# UC3843_SWITCHING_POWER_SUPPLY_V1.net
KiCad netlist of a schematic drawn in Altium Designer
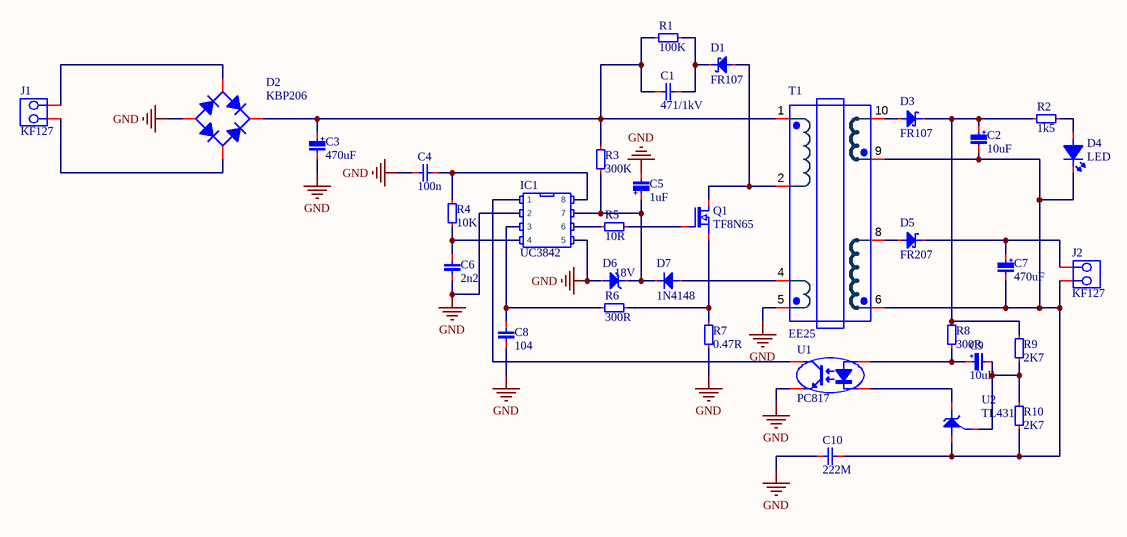
[diagram p0: UC3843_SWITCHING_POWER_SUPPLY_V1.SchDoc]

(export (version "E")
  (design (tool "Eeschema 10.0.6"))
  (components
    (comp (ref "C1")
      (value "471/1kV")
      (footprint "CAP_Ceramic_5MM")
      (libsource (lib "MyAltiumLibrary") (part "Capacitors(Disc)"))
    )
    (comp (ref "C2")
      (value "10uF")
      (footprint "CAP_RAD_D05x11")
      (libsource (lib "MyAltiumLibrary") (part "Capacitor(Radian)"))
    )
    (comp (ref "C3")
      (value "470uF")
      (footprint "CAP_RAD_D10x12.5")
      (libsource (lib "MyAltiumLibrary") (part "Capacitor(Radian)"))
    )
    (comp (ref "C4")
      (value "100n")
      (footprint "CAP_Ceramic_2.5MM")
      (libsource (lib "MyAltiumLibrary") (part "Capacitors(Disc)"))
    )
    (comp (ref "C5")
      (value "1uF")
      (footprint "CAP_RAD_D05x11")
      (libsource (lib "") (part "Capacitor(Radian)_1"))
    )
    (comp (ref "C6")
      (value "2n2")
      (footprint "CAP_Ceramic_2.5MM")
      (libsource (lib "") (part "Capacitors(Disc)_1"))
    )
    (comp (ref "C7")
      (value "470uF")
      (footprint "CAP_RAD_D10x12.5")
      (libsource (lib "MyAltiumLibrary") (part "Capacitor(Radian)"))
    )
    (comp (ref "C8")
      (value "104")
      (footprint "CAP_Ceramic_2.5MM")
      (libsource (lib "") (part "Capacitors(Disc)_1"))
    )
    (comp (ref "C9")
      (value "10uF")
      (footprint "CAP_RAD_D05x11")
      (libsource (lib "") (part "Capacitor(Radian)_2"))
    )
    (comp (ref "C10")
      (value "222M")
      (footprint "CAP_Ceramic_473M_9.65mm")
      (libsource (lib "") (part "Capacitors(Disc)_2"))
    )
    (comp (ref "D1")
      (value "FR107")
      (footprint "DO-204AL-BK")
      (description "1A 1000V")
      (libsource (lib "MyAltiumLibrary") (part "Diode-FR107"))
    )
    (comp (ref "D2")
      (value "KBP206")
      (footprint "DIODE-KBP206")
      (libsource (lib "MyAltiumLibrary") (part "Diode-KBP206"))
    )
    (comp (ref "D3")
      (value "FR107")
      (footprint "DO-204AL-BK")
      (description "1A 1000V")
      (libsource (lib "MyAltiumLibrary") (part "Diode-FR107"))
    )
    (comp (ref "D4") (value "LED") (footprint "LED_5MM") (libsource (lib "MyAltiumLibrary") (part "LED 5MM")))
    (comp (ref "D5")
      (value "FR207")
      (footprint "DO-204AC-BK")
      (libsource (lib "MyAltiumLibrary") (part "Diode-FR207"))
    )
    (comp (ref "D6")
      (value "18V")
      (footprint "DO-204AL-RD")
      (libsource (lib "MyAltiumLibrary") (part "Diode-Zener"))
    )
    (comp (ref "D7")
      (value "1N4148")
      (footprint "DO-204AH-RD")
      (description "The fast switching diode")
      (libsource (lib "MyAltiumLibrary") (part "Diode-1N4148"))
    )
    (comp (ref "IC1")
      (value "UC3842")
      (footprint "DIP-8")
      (description "Operating Frequency up to 500KHz")
      (libsource (lib "MyAltiumLibrary") (part "SMPS-UC3842"))
    )
    (comp (ref "J1")
      (value "KF127")
      (footprint "DG127-5.0-02P-14-00AH")
      (libsource (lib "MyAltiumLibrary") (part "DG127-5.0-02P-14-00AH"))
    )
    (comp (ref "J2")
      (value "KF127")
      (footprint "DG127-5.0-02P-14-00AH")
      (libsource (lib "") (part "DG127-5.0-02P-14-00AH_1"))
    )
    (comp (ref "Q1")
      (value "TF8N65")
      (footprint "TO-220F-HEAT-SINK")
      (description "VDS = 650V\r\n ID (at VGS=10V) 8A\r\n RDS(ON) (at VGS=10V) < 1.15Ω")
      (libsource (lib "MyAltiumLibrary") (part "Mostfet-TF8N65"))
    )
    (comp (ref "R1") (value "100K") (footprint "RES-0.5W-H") (libsource (lib "") (part "Resistors THD_2")))
    (comp (ref "R2") (value "1k5") (footprint "RES-0.25W-H") (libsource (lib "") (part "Resistors THD_2")))
    (comp (ref "R3")
      (value "300K")
      (footprint "RES-1W-V")
      (libsource (lib "MyAltiumLibrary") (part "Resistors THD"))
    )
    (comp (ref "R4")
      (value "10K")
      (footprint "RES-0.25W-H")
      (libsource (lib "MyAltiumLibrary") (part "Resistors THD"))
    )
    (comp (ref "R5") (value "10R") (footprint "RES-0.25W-H") (libsource (lib "") (part "Resistors THD_1")))
    (comp (ref "R6") (value "300R") (footprint "RES-0.25W-H") (libsource (lib "") (part "Resistors THD_1")))
    (comp (ref "R7")
      (value "0.47R")
      (footprint "RES-1W-V")
      (libsource (lib "MyAltiumLibrary") (part "Resistors THD"))
    )
    (comp (ref "R8")
      (value "300R")
      (footprint "RES-0.25W-H")
      (libsource (lib "MyAltiumLibrary") (part "Resistors THD"))
    )
    (comp (ref "R9")
      (value "2K7")
      (footprint "RES-0.25W-H")
      (libsource (lib "MyAltiumLibrary") (part "Resistors THD"))
    )
    (comp (ref "R10")
      (value "2K7")
      (footprint "RES-0.25W-H")
      (libsource (lib "MyAltiumLibrary") (part "Resistors THD"))
    )
    (comp (ref "T1")
      (value "EE25")
      (footprint "TRANSFORMER-EE25-10-6-VERTICAL(5+5)")
      (libsource (lib "MyAltiumLibrary") (part "TRANS-EE25-10-6-VERTICAL(5+5)"))
    )
    (comp (ref "U1")
      (value "PC817")
      (footprint "PC817-DIP")
      (libsource (lib "MyAltiumLibrary") (part "Opto-PC817"))
    )
    (comp (ref "U2")
      (value "TL431")
      (footprint "TO-92")
      (libsource (lib "MyAltiumLibrary") (part "Ic-TL431"))
    )
  )
  (nets
    (net (code "1") (name "GND") (class "Default")
      (node (ref "C10") (pin "1") (pinfunction "1_1") (pintype "passive"))
      (node (ref "C3") (pin "2") (pinfunction "2_2") (pintype "passive"))
      (node (ref "C4") (pin "2") (pinfunction "2_2") (pintype "passive"))
      (node (ref "C5") (pin "2") (pinfunction "2_2") (pintype "passive"))
      (node (ref "C6") (pin "1") (pinfunction "1_1") (pintype "passive"))
      (node (ref "C8") (pin "1") (pinfunction "1_1") (pintype "passive"))
      (node (ref "D2") (pin "4") (pinfunction "-_4") (pintype "passive"))
      (node (ref "D6") (pin "1") (pinfunction "1_1") (pintype "passive"))
      (node (ref "IC1") (pin "2") (pinfunction "2_2") (pintype "passive"))
      (node (ref "IC1") (pin "5") (pinfunction "5_5") (pintype "passive"))
      (node (ref "R7") (pin "1") (pinfunction "1_1") (pintype "passive"))
      (node (ref "T1") (pin "5") (pinfunction "6_5") (pintype "passive"))
      (node (ref "U1") (pin "3") (pinfunction "E_3") (pintype "passive"))
    )
    (net (code "2") (name "Net-(C1-Pad1)") (class "Default")
      (node (ref "C1") (pin "1") (pinfunction "1_1") (pintype "passive"))
      (node (ref "D1") (pin "2") (pinfunction "2_2") (pintype "passive"))
      (node (ref "R1") (pin "1") (pinfunction "1_1") (pintype "passive"))
    )
    (net (code "3") (name "Net-(C2-Pad1)") (class "Default")
      (node (ref "C2") (pin "1") (pinfunction "1_1") (pintype "passive"))
      (node (ref "D3") (pin "2") (pinfunction "2_2") (pintype "passive"))
      (node (ref "R2") (pin "2") (pinfunction "2_2") (pintype "passive"))
      (node (ref "R8") (pin "2") (pinfunction "2_2") (pintype "passive"))
      (node (ref "R9") (pin "2") (pinfunction "2_2") (pintype "passive"))
    )
    (net (code "4") (name "Net-(C4-Pad1)") (class "Default")
      (node (ref "C4") (pin "1") (pinfunction "1_1") (pintype "passive"))
      (node (ref "IC1") (pin "8") (pinfunction "8_8") (pintype "passive"))
      (node (ref "R4") (pin "2") (pinfunction "2_2") (pintype "passive"))
    )
    (net (code "5") (name "Net-(C5-Pad1)") (class "Default")
      (node (ref "C5") (pin "1") (pinfunction "1_1") (pintype "passive"))
      (node (ref "D6") (pin "2") (pinfunction "2_2") (pintype "passive"))
      (node (ref "D7") (pin "2") (pinfunction "2_2") (pintype "passive"))
      (node (ref "IC1") (pin "7") (pinfunction "7_7") (pintype "passive"))
      (node (ref "R3") (pin "1") (pinfunction "1_1") (pintype "passive"))
    )
    (net (code "6") (name "Net-(C6-Pad2)") (class "Default")
      (node (ref "C6") (pin "2") (pinfunction "2_2") (pintype "passive"))
      (node (ref "IC1") (pin "4") (pinfunction "4_4") (pintype "passive"))
      (node (ref "R4") (pin "1") (pinfunction "1_1") (pintype "passive"))
    )
    (net (code "7") (name "Net-(C7-Pad1)") (class "Default")
      (node (ref "C7") (pin "1") (pinfunction "1_1") (pintype "passive"))
      (node (ref "D5") (pin "2") (pinfunction "2_2") (pintype "passive"))
      (node (ref "J2") (pin "1") (pinfunction "1_1") (pintype "passive"))
    )
    (net (code "8") (name "Net-(C8-Pad2)") (class "Default")
      (node (ref "C8") (pin "2") (pinfunction "2_2") (pintype "passive"))
      (node (ref "IC1") (pin "3") (pinfunction "3_3") (pintype "passive"))
      (node (ref "R6") (pin "1") (pinfunction "1_1") (pintype "passive"))
    )
    (net (code "9") (name "Net-(C9-Pad2)") (class "Default")
      (node (ref "C9") (pin "2") (pinfunction "2_2") (pintype "passive"))
      (node (ref "R10") (pin "2") (pinfunction "2_2") (pintype "passive"))
      (node (ref "R9") (pin "1") (pinfunction "1_1") (pintype "passive"))
      (node (ref "U2") (pin "1") (pinfunction "1_1") (pintype "passive"))
    )
    (net (code "10") (name "Net-(D2-+)") (class "Default")
      (node (ref "C1") (pin "2") (pinfunction "2_2") (pintype "passive"))
      (node (ref "C3") (pin "1") (pinfunction "1_1") (pintype "passive"))
      (node (ref "D2") (pin "1") (pinfunction "+_1") (pintype "passive"))
      (node (ref "R1") (pin "2") (pinfunction "2_2") (pintype "passive"))
      (node (ref "R3") (pin "2") (pinfunction "2_2") (pintype "passive"))
      (node (ref "T1") (pin "1") (pinfunction "1_1") (pintype "passive"))
    )
    (net (code "11") (name "Net-(D2-AC-Pad2)") (class "Default")
      (node (ref "D2") (pin "2") (pinfunction "AC_2") (pintype "passive"))
      (node (ref "J1") (pin "2") (pinfunction "2_2") (pintype "passive"))
    )
    (net (code "12") (name "Net-(D2-AC-Pad3)") (class "Default")
      (node (ref "D2") (pin "3") (pinfunction "AC_3") (pintype "passive"))
      (node (ref "J1") (pin "1") (pinfunction "1_1") (pintype "passive"))
    )
    (net (code "13") (name "Net-(D3-Pad1)") (class "Default")
      (node (ref "D3") (pin "1") (pinfunction "1_1") (pintype "passive"))
      (node (ref "T1") (pin "10") (pinfunction "10_10") (pintype "passive"))
    )
    (net (code "14") (name "Net-(D4-A)") (class "Default")
      (node (ref "D4") (pin "1") (pinfunction "A_1") (pintype "passive"))
      (node (ref "R2") (pin "1") (pinfunction "1_1") (pintype "passive"))
    )
    (net (code "15") (name "Net-(D4-K)") (class "Default")
      (node (ref "C10") (pin "2") (pinfunction "2_2") (pintype "passive"))
      (node (ref "C2") (pin "2") (pinfunction "2_2") (pintype "passive"))
      (node (ref "C7") (pin "2") (pinfunction "2_2") (pintype "passive"))
      (node (ref "D4") (pin "2") (pinfunction "K_2") (pintype "passive"))
      (node (ref "J2") (pin "2") (pinfunction "2_2") (pintype "passive"))
      (node (ref "R10") (pin "1") (pinfunction "1_1") (pintype "passive"))
      (node (ref "T1") (pin "6") (pinfunction "6_6") (pintype "passive"))
      (node (ref "T1") (pin "9") (pinfunction "9_9") (pintype "passive"))
      (node (ref "U2") (pin "2") (pinfunction "2_2") (pintype "passive"))
    )
    (net (code "16") (name "Net-(D5-Pad1)") (class "Default")
      (node (ref "D5") (pin "1") (pinfunction "1_1") (pintype "passive"))
      (node (ref "T1") (pin "8") (pinfunction "8_8") (pintype "passive"))
    )
    (net (code "17") (name "Net-(D7-Pad1)") (class "Default")
      (node (ref "D7") (pin "1") (pinfunction "1_1") (pintype "passive"))
      (node (ref "T1") (pin "4") (pinfunction "4_4") (pintype "passive"))
    )
    (net (code "18") (name "Net-(IC1-Pad6)") (class "Default")
      (node (ref "IC1") (pin "6") (pinfunction "6_6") (pintype "passive"))
      (node (ref "R5") (pin "1") (pinfunction "1_1") (pintype "passive"))
    )
    (net (code "19") (name "Net-(Q1-D)") (class "Default")
      (node (ref "D1") (pin "1") (pinfunction "1_1") (pintype "passive"))
      (node (ref "Q1") (pin "2") (pinfunction "D_2") (pintype "passive"))
      (node (ref "T1") (pin "2") (pinfunction "2_2") (pintype "passive"))
    )
    (net (code "20") (name "Net-(Q1-G)") (class "Default")
      (node (ref "Q1") (pin "1") (pinfunction "G_1") (pintype "passive"))
      (node (ref "R5") (pin "2") (pinfunction "2_2") (pintype "passive"))
    )
    (net (code "21") (name "Net-(Q1-S)") (class "Default")
      (node (ref "Q1") (pin "3") (pinfunction "S_3") (pintype "passive"))
      (node (ref "R6") (pin "2") (pinfunction "2_2") (pintype "passive"))
      (node (ref "R7") (pin "2") (pinfunction "2_2") (pintype "passive"))
    )
    (net (code "22") (name "Net-(U1-A)") (class "Default")
      (node (ref "C9") (pin "1") (pinfunction "1_1") (pintype "passive"))
      (node (ref "R8") (pin "1") (pinfunction "1_1") (pintype "passive"))
      (node (ref "U1") (pin "1") (pinfunction "A_1") (pintype "passive"))
    )
    (net (code "23") (name "Net-(U1-C)") (class "Default")
      (node (ref "IC1") (pin "1") (pinfunction "1_1") (pintype "passive"))
      (node (ref "U1") (pin "4") (pinfunction "C_4") (pintype "passive"))
    )
    (net (code "24") (name "Net-(U1-K)") (class "Default")
      (node (ref "U1") (pin "2") (pinfunction "K_2") (pintype "passive"))
      (node (ref "U2") (pin "3") (pinfunction "3_3") (pintype "passive"))
    )
  )
)
